# BKU.net
KiCad netlist of a schematic drawn in EAGLE
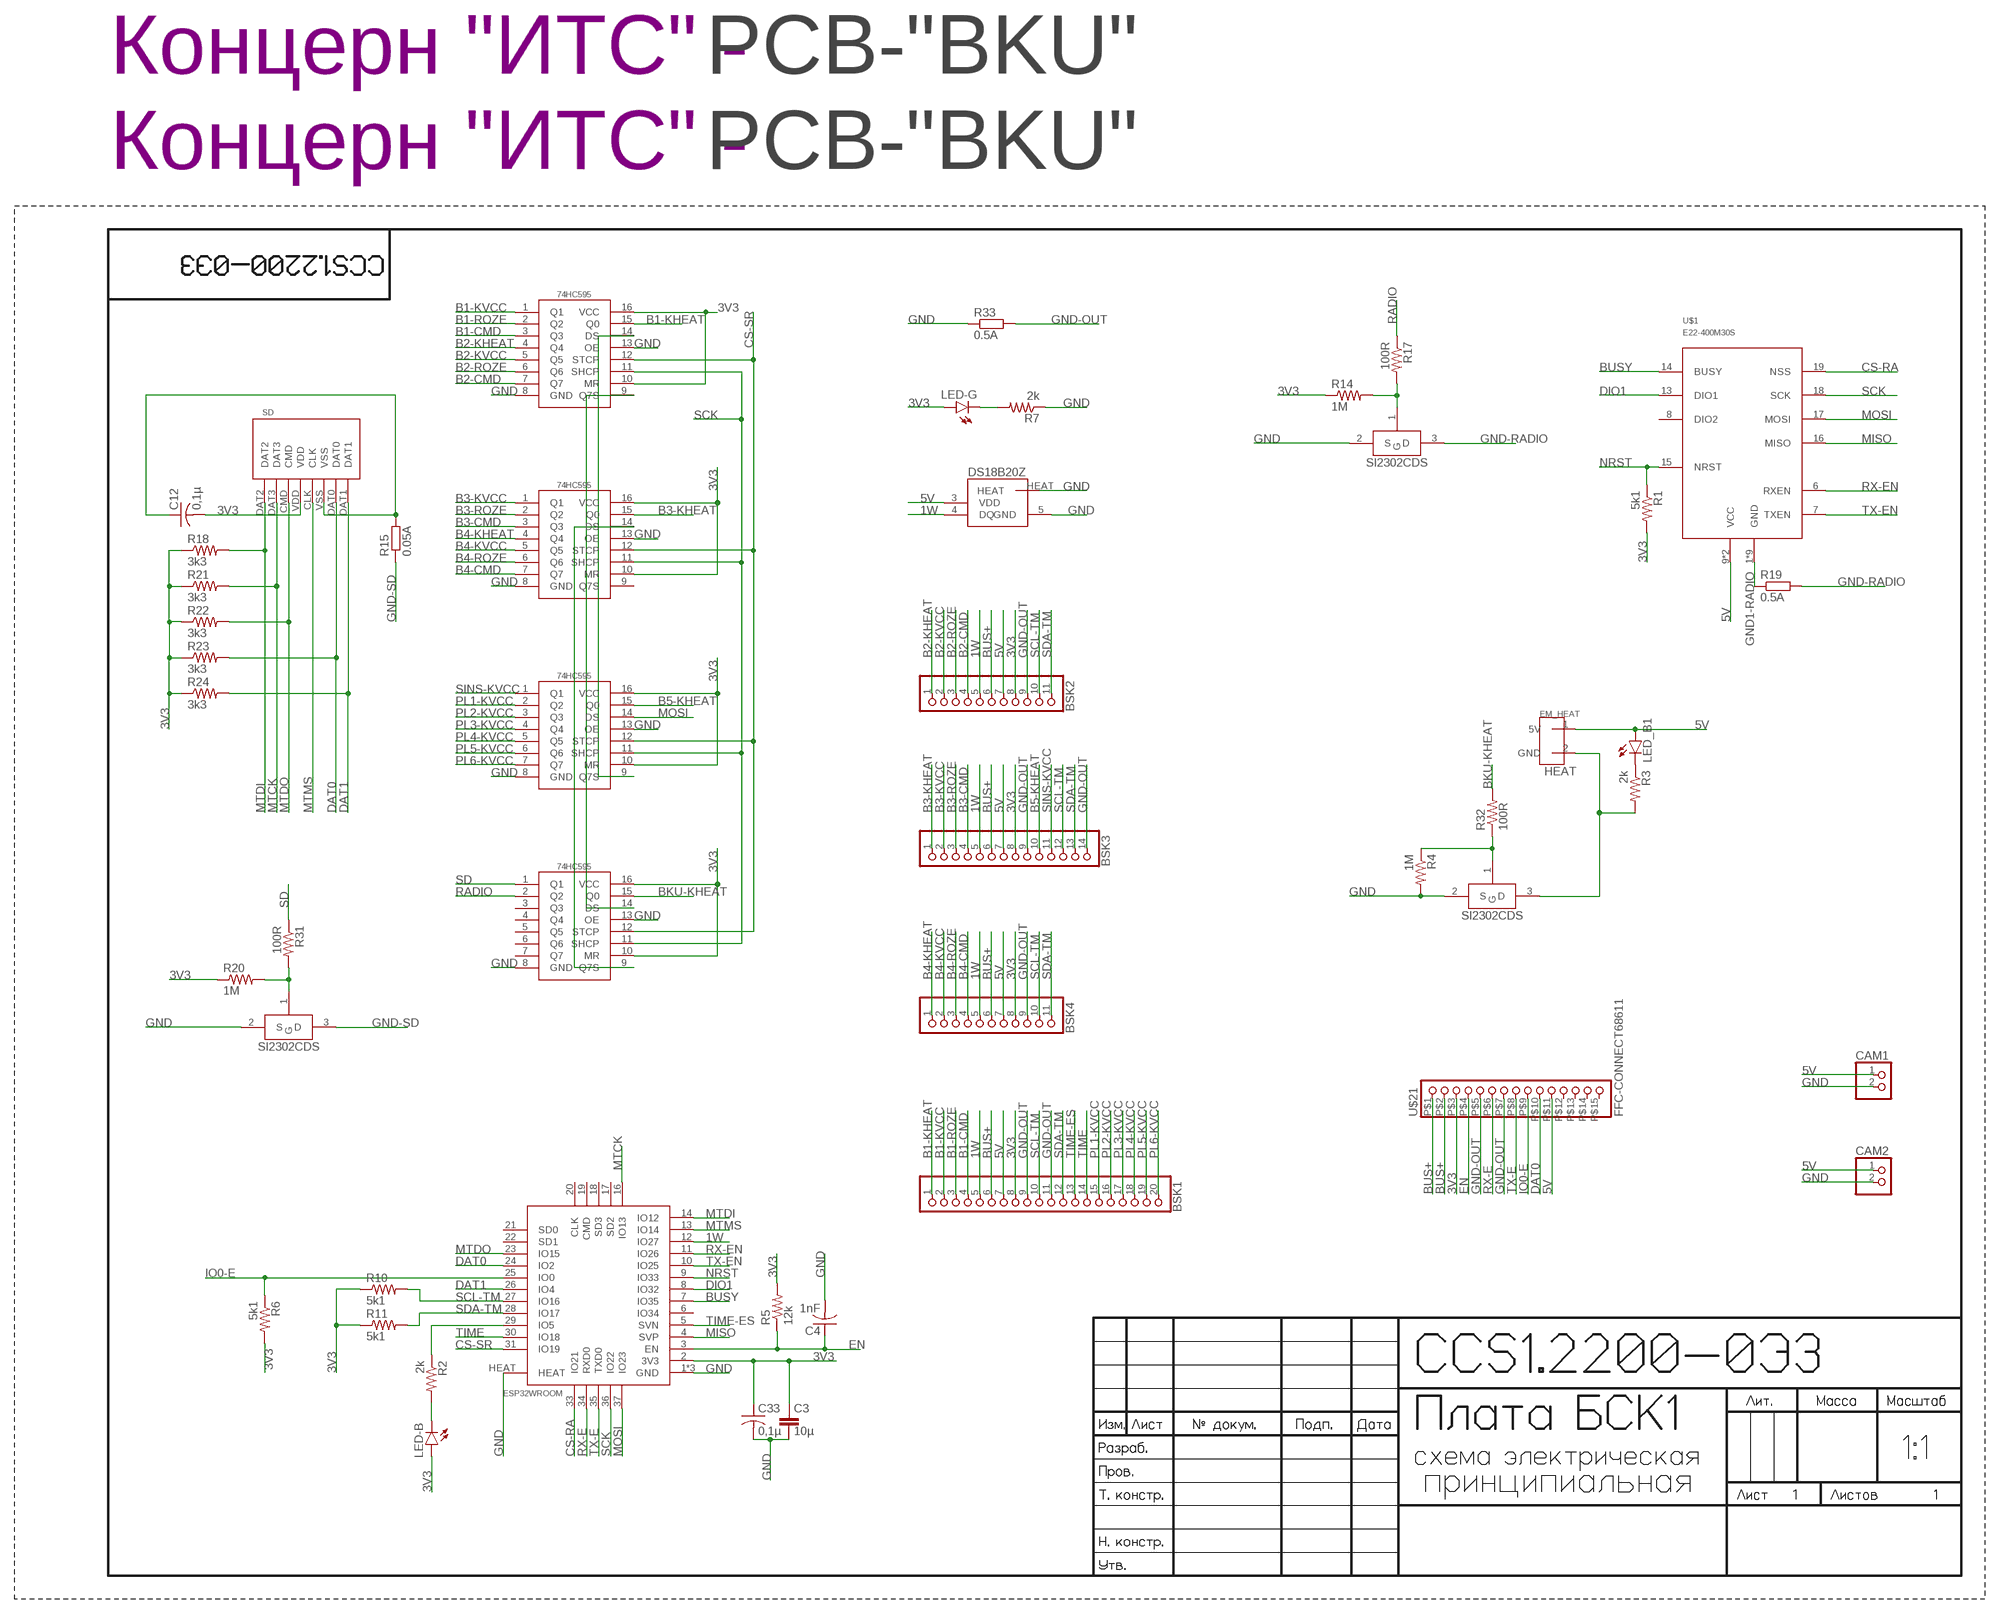
[diagram p0: schematic, sheet 1, part 1 of 2]
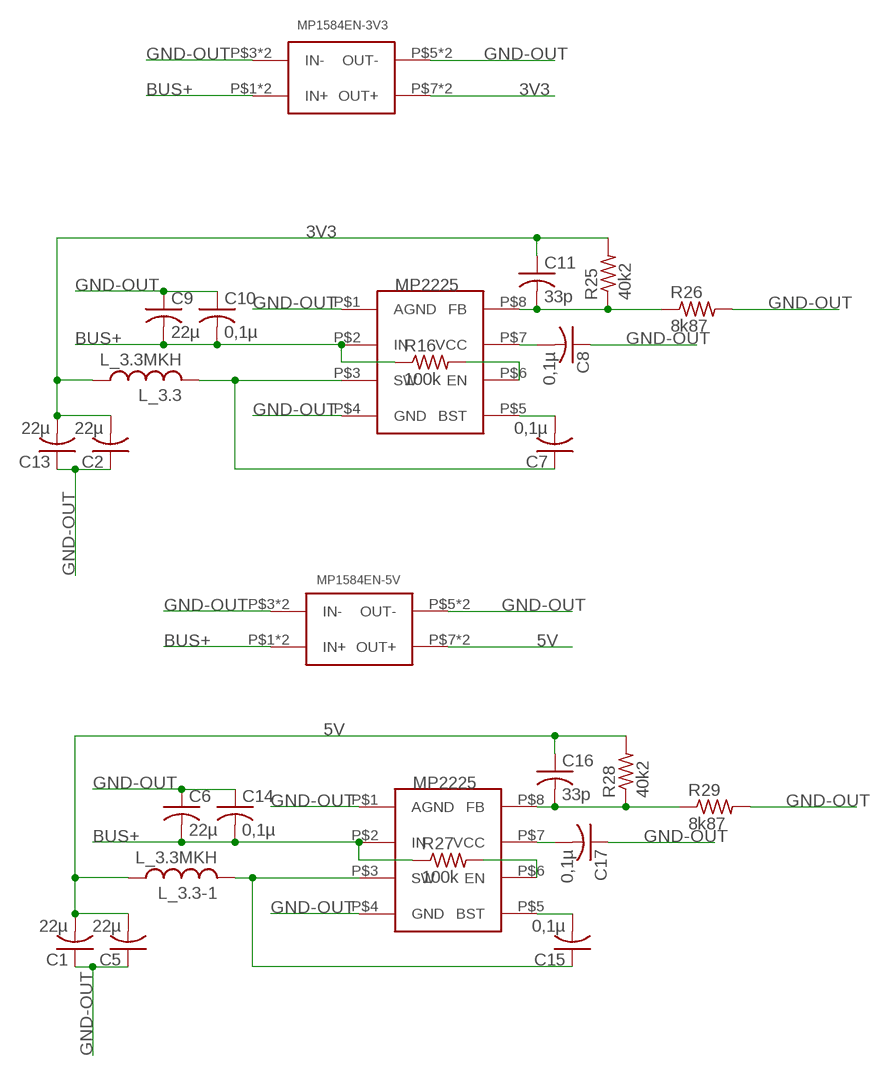
[diagram p1: schematic, sheet 1, part 2 of 2]

(export (version "E")
  (design (tool "Eeschema 10.0.6"))
  (components
    (comp (ref "74HC595#1")
      (value "74HC595")
      (footprint "eagle-import:TSSOP16")
      (libsource (lib "eagle-import") (part "74HC595"))
    )
    (comp (ref "74HC595#2")
      (value "74HC595")
      (footprint "eagle-import:TSSOP16")
      (libsource (lib "eagle-import") (part "74HC595"))
    )
    (comp (ref "74HC595#3")
      (value "74HC595")
      (footprint "eagle-import:TSSOP16")
      (libsource (lib "eagle-import") (part "74HC595"))
    )
    (comp (ref "74HC595#4")
      (value "74HC595")
      (footprint "eagle-import:TSSOP16")
      (libsource (lib "eagle-import") (part "74HC595"))
    )
    (comp (ref "BSK1")
      (value "PINHD-1X20")
      (footprint "eagle-import:1X20")
      (libsource (lib "eagle-import") (part "PINHD-1X20"))
    )
    (comp (ref "BSK2")
      (value "PINHD-1X11")
      (footprint "eagle-import:1X11")
      (libsource (lib "eagle-import") (part "PINHD-1X11"))
    )
    (comp (ref "BSK3")
      (value "PINHD-1X14")
      (footprint "eagle-import:1X14")
      (libsource (lib "eagle-import") (part "PINHD-1X14"))
    )
    (comp (ref "BSK4")
      (value "PINHD-1X11")
      (footprint "eagle-import:1X11")
      (libsource (lib "eagle-import") (part "PINHD-1X11"))
    )
    (comp (ref "C1")
      (value "22µ")
      (footprint "eagle-import:C1206")
      (libsource (lib "eagle-import") (part "C-USC1206"))
    )
    (comp (ref "C2")
      (value "22µ")
      (footprint "eagle-import:C1206")
      (libsource (lib "eagle-import") (part "C-USC1206"))
    )
    (comp (ref "C3")
      (value "10µ")
      (footprint "eagle-import:C1206")
      (libsource (lib "eagle-import") (part "C-EUC1206"))
    )
    (comp (ref "C4")
      (value "1nF")
      (footprint "eagle-import:C0603")
      (libsource (lib "eagle-import") (part "C-USC0603"))
    )
    (comp (ref "C5")
      (value "22µ")
      (footprint "eagle-import:C1206")
      (libsource (lib "eagle-import") (part "C-USC1206"))
    )
    (comp (ref "C6")
      (value "22µ")
      (footprint "eagle-import:C1206")
      (libsource (lib "eagle-import") (part "C-USC1206"))
    )
    (comp (ref "C7")
      (value "0,1µ")
      (footprint "eagle-import:C0603")
      (libsource (lib "eagle-import") (part "C-USC0603"))
    )
    (comp (ref "C8")
      (value "0,1µ")
      (footprint "eagle-import:C0603")
      (libsource (lib "eagle-import") (part "C-USC0603"))
    )
    (comp (ref "C9")
      (value "22µ")
      (footprint "eagle-import:C1206")
      (libsource (lib "eagle-import") (part "C-USC1206"))
    )
    (comp (ref "C10")
      (value "0,1µ")
      (footprint "eagle-import:C0603")
      (libsource (lib "eagle-import") (part "C-USC0603"))
    )
    (comp (ref "C11")
      (value "33p")
      (footprint "eagle-import:C0603")
      (libsource (lib "eagle-import") (part "C-USC0603"))
    )
    (comp (ref "C12")
      (value "0,1µ")
      (footprint "eagle-import:C0603")
      (libsource (lib "eagle-import") (part "C-USC0603"))
    )
    (comp (ref "C13")
      (value "22µ")
      (footprint "eagle-import:C1206")
      (libsource (lib "eagle-import") (part "C-USC1206"))
    )
    (comp (ref "C14")
      (value "0,1µ")
      (footprint "eagle-import:C0603")
      (libsource (lib "eagle-import") (part "C-USC0603"))
    )
    (comp (ref "C15")
      (value "0,1µ")
      (footprint "eagle-import:C0603")
      (libsource (lib "eagle-import") (part "C-USC0603"))
    )
    (comp (ref "C16")
      (value "33p")
      (footprint "eagle-import:C0603")
      (libsource (lib "eagle-import") (part "C-USC0603"))
    )
    (comp (ref "C17")
      (value "0,1µ")
      (footprint "eagle-import:C0603")
      (libsource (lib "eagle-import") (part "C-USC0603"))
    )
    (comp (ref "C33")
      (value "0,1µ")
      (footprint "eagle-import:C0603")
      (libsource (lib "eagle-import") (part "C-USC0603"))
    )
    (comp (ref "CAM1")
      (value "PINHD-1X2")
      (footprint "eagle-import:1X02")
      (libsource (lib "eagle-import") (part "PINHD-1X2"))
    )
    (comp (ref "CAM2")
      (value "PINHD-1X2")
      (footprint "eagle-import:1X02")
      (libsource (lib "eagle-import") (part "PINHD-1X2"))
    )
    (comp (ref "LED-B")
      (value "LEDCHIPLED_0603")
      (footprint "eagle-import:CHIPLED_0603")
      (libsource (lib "eagle-import") (part "LEDCHIPLED_0603"))
    )
    (comp (ref "LED-G")
      (value "LEDCHIPLED_0603")
      (footprint "eagle-import:CHIPLED_0603")
      (libsource (lib "eagle-import") (part "LEDCHIPLED_0603"))
    )
    (comp (ref "LED_B1")
      (value "LEDCHIPLED_0603")
      (footprint "eagle-import:CHIPLED_0603")
      (libsource (lib "eagle-import") (part "LEDCHIPLED_0603"))
    )
    (comp (ref "L_3.3")
      (value "L_3.3MKH")
      (footprint "eagle-import:L_SPM5020")
      (libsource (lib "eagle-import") (part "L_3.3MKH_5X5"))
    )
    (comp (ref "L_3.3-1")
      (value "L_3.3MKH")
      (footprint "eagle-import:L_SPM5020")
      (libsource (lib "eagle-import") (part "L_3.3MKH_5X5"))
    )
    (comp (ref "MP1584EN-3V3")
      (value "MP1584-B")
      (footprint "eagle-import:MP1584-B")
      (libsource (lib "eagle-import") (part "MP1584-B"))
    )
    (comp (ref "MP1584EN-5V")
      (value "MP1584-B")
      (footprint "eagle-import:MP1584-B")
      (libsource (lib "eagle-import") (part "MP1584-B"))
    )
    (comp (ref "MP2225-3V3")
      (value "MP2225")
      (footprint "eagle-import:TSOT23-8")
      (libsource (lib "eagle-import") (part "MP2225"))
    )
    (comp (ref "MP2225-5V")
      (value "MP2225")
      (footprint "eagle-import:TSOT23-8")
      (libsource (lib "eagle-import") (part "MP2225"))
    )
    (comp (ref "R1")
      (value "5k1")
      (footprint "eagle-import:R0603")
      (libsource (lib "eagle-import") (part "resistor_348_R-US_R0603"))
    )
    (comp (ref "R2")
      (value "2k")
      (footprint "eagle-import:R0603")
      (libsource (lib "eagle-import") (part "resistor_348_R-US_R0603"))
    )
    (comp (ref "R3")
      (value "2k")
      (footprint "eagle-import:R0603")
      (libsource (lib "eagle-import") (part "R-US_R0603"))
    )
    (comp (ref "R4")
      (value "1M")
      (footprint "eagle-import:R0603")
      (libsource (lib "eagle-import") (part "R-US_R0603"))
    )
    (comp (ref "R5")
      (value "12k")
      (footprint "eagle-import:R0603")
      (libsource (lib "eagle-import") (part "resistor_348_R-US_R0603"))
    )
    (comp (ref "R6")
      (value "5k1")
      (footprint "eagle-import:R0603")
      (libsource (lib "eagle-import") (part "resistor_348_R-US_R0603"))
    )
    (comp (ref "R7")
      (value "2k")
      (footprint "eagle-import:R0603")
      (libsource (lib "eagle-import") (part "resistor_348_R-US_R0603"))
    )
    (comp (ref "R10")
      (value "5k1")
      (footprint "eagle-import:R0603")
      (libsource (lib "eagle-import") (part "resistor_348_R-US_R0603"))
    )
    (comp (ref "R11")
      (value "5k1")
      (footprint "eagle-import:R0603")
      (libsource (lib "eagle-import") (part "resistor_348_R-US_R0603"))
    )
    (comp (ref "R14")
      (value "1M")
      (footprint "eagle-import:R0603")
      (libsource (lib "eagle-import") (part "R-US_R0603"))
    )
    (comp (ref "R15")
      (value "0.05A")
      (footprint "eagle-import:R1210")
      (libsource (lib "eagle-import") (part "R-EU_R1210"))
    )
    (comp (ref "R16")
      (value "100k")
      (footprint "eagle-import:R0603")
      (libsource (lib "eagle-import") (part "resistor_348_R-US_R0603"))
    )
    (comp (ref "R17")
      (value "100R")
      (footprint "eagle-import:R0603")
      (libsource (lib "eagle-import") (part "R-US_R0603"))
    )
    (comp (ref "R18")
      (value "3k3")
      (footprint "eagle-import:R0603")
      (libsource (lib "eagle-import") (part "resistor_348_R-US_R0603"))
    )
    (comp (ref "R19")
      (value "0.5A")
      (footprint "eagle-import:R1210")
      (libsource (lib "eagle-import") (part "R-EU_R1210"))
    )
    (comp (ref "R20")
      (value "1M")
      (footprint "eagle-import:R0603")
      (libsource (lib "eagle-import") (part "R-US_R0603"))
    )
    (comp (ref "R21")
      (value "3k3")
      (footprint "eagle-import:R0603")
      (libsource (lib "eagle-import") (part "resistor_348_R-US_R0603"))
    )
    (comp (ref "R22")
      (value "3k3")
      (footprint "eagle-import:R0603")
      (libsource (lib "eagle-import") (part "resistor_348_R-US_R0603"))
    )
    (comp (ref "R23")
      (value "3k3")
      (footprint "eagle-import:R0603")
      (libsource (lib "eagle-import") (part "resistor_348_R-US_R0603"))
    )
    (comp (ref "R24")
      (value "3k3")
      (footprint "eagle-import:R0603")
      (libsource (lib "eagle-import") (part "resistor_348_R-US_R0603"))
    )
    (comp (ref "R25")
      (value "40k2")
      (footprint "eagle-import:R0603")
      (libsource (lib "eagle-import") (part "resistor_348_R-US_R0603"))
    )
    (comp (ref "R26")
      (value "8k87")
      (footprint "eagle-import:R0603")
      (libsource (lib "eagle-import") (part "resistor_348_R-US_R0603"))
    )
    (comp (ref "R27")
      (value "100k")
      (footprint "eagle-import:R0603")
      (libsource (lib "eagle-import") (part "resistor_348_R-US_R0603"))
    )
    (comp (ref "R28")
      (value "40k2")
      (footprint "eagle-import:R0603")
      (libsource (lib "eagle-import") (part "resistor_348_R-US_R0603"))
    )
    (comp (ref "R29")
      (value "8k87")
      (footprint "eagle-import:R0603")
      (libsource (lib "eagle-import") (part "resistor_348_R-US_R0603"))
    )
    (comp (ref "R31")
      (value "100R")
      (footprint "eagle-import:R0603")
      (libsource (lib "eagle-import") (part "R-US_R0603"))
    )
    (comp (ref "R32")
      (value "100R")
      (footprint "eagle-import:R0603")
      (libsource (lib "eagle-import") (part "R-US_R0603"))
    )
    (comp (ref "R33")
      (value "0.5A")
      (footprint "eagle-import:R1210")
      (libsource (lib "eagle-import") (part "R-EU_R1210"))
    )
    (comp (ref "SD") (value "SD") (footprint "eagle-import:SD") (libsource (lib "eagle-import") (part "SD")))
    (comp (ref "U$1")
      (value "E22-400M30S")
      (footprint "eagle-import:E22-400M30S")
      (libsource (lib "eagle-import") (part "E22-400M30S"))
    )
    (comp (ref "U$2")
      (value "PCB-\"BKU\"")
      (footprint "eagle-import:ITS-LOGO")
      (libsource (lib "eagle-import") (part "ITS-LOGOPCB-{dblquote}{dblquote}"))
    )
    (comp (ref "U$3")
      (value "SI2302CDS")
      (footprint "eagle-import:SOT23-3")
      (libsource (lib "eagle-import") (part "SI2302CDS"))
    )
    (comp (ref "U$4")
      (value "SI2302CDS")
      (footprint "eagle-import:SOT23-3")
      (libsource (lib "eagle-import") (part "SI2302CDS"))
    )
    (comp (ref "U$5")
      (value "DS18B20Z")
      (footprint "eagle-import:SOIC8+HEAT_S")
      (libsource (lib "eagle-import") (part "DS18B20Z"))
    )
    (comp (ref "U$6")
      (value "PCB-\"BKU\"")
      (footprint "eagle-import:ITS-LOGO")
      (libsource (lib "eagle-import") (part "ITS-LOGOPCB-{dblquote}{dblquote}"))
    )
    (comp (ref "U$13")
      (value "ESP32WROOM")
      (footprint "eagle-import:ESP32WROOM")
      (libsource (lib "eagle-import") (part "ESP32WROOM"))
    )
    (comp (ref "U$21")
      (value "FFC-CONNECT68611")
      (footprint "eagle-import:68611")
      (libsource (lib "eagle-import") (part "FFC-CONNECT68611"))
    )
    (comp (ref "U$23")
      (value "SI2302CDS")
      (footprint "eagle-import:SOT23-3")
      (libsource (lib "eagle-import") (part "SI2302CDS"))
    )
    (comp (ref "U$24")
      (value "EM_HEAT")
      (footprint "eagle-import:EM_HEAT")
      (libsource (lib "eagle-import") (part "EM_HEAT"))
    )
  )
  (nets
    (net (code "1") (name "/1W") (class "Default")
      (node (ref "BSK1") (pin "5") (pinfunction "5_5") (pintype "passive"))
      (node (ref "BSK2") (pin "5") (pinfunction "5_5") (pintype "passive"))
      (node (ref "BSK3") (pin "5") (pinfunction "5_5") (pintype "passive"))
      (node (ref "BSK4") (pin "5") (pinfunction "5_5") (pintype "passive"))
      (node (ref "U$13") (pin "12") (pinfunction "IO27_12") (pintype "bidirectional"))
      (node (ref "U$5") (pin "4") (pinfunction "DQ_4") (pintype "bidirectional"))
    )
    (net (code "2") (name "/3V3") (class "Default")
      (node (ref "74HC595#1") (pin "10") (pinfunction "MR_10") (pintype "bidirectional"))
      (node (ref "74HC595#1") (pin "16") (pinfunction "VCC_16") (pintype "bidirectional"))
      (node (ref "74HC595#2") (pin "10") (pinfunction "MR_10") (pintype "bidirectional"))
      (node (ref "74HC595#2") (pin "16") (pinfunction "VCC_16") (pintype "bidirectional"))
      (node (ref "74HC595#3") (pin "10") (pinfunction "MR_10") (pintype "bidirectional"))
      (node (ref "74HC595#3") (pin "16") (pinfunction "VCC_16") (pintype "bidirectional"))
      (node (ref "74HC595#4") (pin "10") (pinfunction "MR_10") (pintype "bidirectional"))
      (node (ref "74HC595#4") (pin "16") (pinfunction "VCC_16") (pintype "bidirectional"))
      (node (ref "BSK1") (pin "8") (pinfunction "8_8") (pintype "passive"))
      (node (ref "BSK2") (pin "8") (pinfunction "8_8") (pintype "passive"))
      (node (ref "BSK3") (pin "8") (pinfunction "8_8") (pintype "passive"))
      (node (ref "BSK4") (pin "8") (pinfunction "8_8") (pintype "passive"))
      (node (ref "C11") (pin "1") (pinfunction "1_1") (pintype "passive"))
      (node (ref "C12") (pin "2") (pinfunction "2_2") (pintype "passive"))
      (node (ref "C13") (pin "2") (pinfunction "2_2") (pintype "passive"))
      (node (ref "C2") (pin "2") (pinfunction "2_2") (pintype "passive"))
      (node (ref "C3") (pin "1") (pinfunction "1_1") (pintype "passive"))
      (node (ref "C33") (pin "1") (pinfunction "1_1") (pintype "passive"))
      (node (ref "LED-B") (pin "A") (pinfunction "A_A") (pintype "passive"))
      (node (ref "LED-G") (pin "A") (pinfunction "A_A") (pintype "passive"))
      (node (ref "L_3.3") (pin "P$1") (pinfunction "1_P$1") (pintype "passive"))
      (node (ref "MP1584EN-3V3") (pin "P$7") (pinfunction "OUT+_P$7") (pintype "bidirectional"))
      (node (ref "MP1584EN-3V3") (pin "P$8") (pinfunction "OUT+_P$8") (pintype "bidirectional"))
      (node (ref "R1") (pin "2") (pinfunction "2_2") (pintype "passive"))
      (node (ref "R10") (pin "1") (pinfunction "1_1") (pintype "passive"))
      (node (ref "R11") (pin "1") (pinfunction "1_1") (pintype "passive"))
      (node (ref "R14") (pin "1") (pinfunction "1_1") (pintype "passive"))
      (node (ref "R18") (pin "1") (pinfunction "1_1") (pintype "passive"))
      (node (ref "R20") (pin "1") (pinfunction "1_1") (pintype "passive"))
      (node (ref "R21") (pin "1") (pinfunction "1_1") (pintype "passive"))
      (node (ref "R22") (pin "1") (pinfunction "1_1") (pintype "passive"))
      (node (ref "R23") (pin "1") (pinfunction "1_1") (pintype "passive"))
      (node (ref "R24") (pin "1") (pinfunction "1_1") (pintype "passive"))
      (node (ref "R25") (pin "2") (pinfunction "2_2") (pintype "passive"))
      (node (ref "R5") (pin "2") (pinfunction "2_2") (pintype "passive"))
      (node (ref "R6") (pin "2") (pinfunction "2_2") (pintype "passive"))
      (node (ref "SD") (pin "VDD") (pinfunction "VDD_VDD") (pintype "bidirectional"))
      (node (ref "U$13") (pin "2") (pinfunction "3V3_2") (pintype "bidirectional"))
      (node (ref "U$21") (pin "P$3") (pinfunction "3_P$3") (pintype "passive"))
    )
    (net (code "3") (name "/5V") (class "Default")
      (node (ref "BSK1") (pin "7") (pinfunction "7_7") (pintype "passive"))
      (node (ref "BSK2") (pin "7") (pinfunction "7_7") (pintype "passive"))
      (node (ref "BSK3") (pin "7") (pinfunction "7_7") (pintype "passive"))
      (node (ref "BSK4") (pin "7") (pinfunction "7_7") (pintype "passive"))
      (node (ref "C1") (pin "2") (pinfunction "2_2") (pintype "passive"))
      (node (ref "C16") (pin "1") (pinfunction "1_1") (pintype "passive"))
      (node (ref "C5") (pin "2") (pinfunction "2_2") (pintype "passive"))
      (node (ref "CAM1") (pin "1") (pinfunction "1_1") (pintype "passive"))
      (node (ref "CAM2") (pin "1") (pinfunction "1_1") (pintype "passive"))
      (node (ref "LED_B1") (pin "A") (pinfunction "A_A") (pintype "passive"))
      (node (ref "L_3.3-1") (pin "P$1") (pinfunction "1_P$1") (pintype "passive"))
      (node (ref "MP1584EN-5V") (pin "P$7") (pinfunction "OUT+_P$7") (pintype "bidirectional"))
      (node (ref "MP1584EN-5V") (pin "P$8") (pinfunction "OUT+_P$8") (pintype "bidirectional"))
      (node (ref "R28") (pin "2") (pinfunction "2_2") (pintype "passive"))
      (node (ref "U$1") (pin "10") (pinfunction "VCC_10") (pintype "power_in"))
      (node (ref "U$1") (pin "9") (pinfunction "VCC_9") (pintype "power_in"))
      (node (ref "U$21") (pin "P$11") (pinfunction "11_P$11") (pintype "passive"))
      (node (ref "U$24") (pin "1") (pinfunction "5V_1") (pintype "bidirectional"))
      (node (ref "U$5") (pin "3") (pinfunction "VDD_3") (pintype "bidirectional"))
    )
    (net (code "4") (name "/B1-CMD") (class "Default")
      (node (ref "74HC595#1") (pin "3") (pinfunction "Q3_3") (pintype "bidirectional"))
      (node (ref "BSK1") (pin "4") (pinfunction "4_4") (pintype "passive"))
    )
    (net (code "5") (name "/B1-KHEAT") (class "Default")
      (node (ref "74HC595#1") (pin "15") (pinfunction "Q0_15") (pintype "bidirectional"))
      (node (ref "BSK1") (pin "1") (pinfunction "1_1") (pintype "passive"))
    )
    (net (code "6") (name "/B1-KVCC") (class "Default")
      (node (ref "74HC595#1") (pin "1") (pinfunction "Q1_1") (pintype "bidirectional"))
      (node (ref "BSK1") (pin "2") (pinfunction "2_2") (pintype "passive"))
    )
    (net (code "7") (name "/B1-ROZE") (class "Default")
      (node (ref "74HC595#1") (pin "2") (pinfunction "Q2_2") (pintype "bidirectional"))
      (node (ref "BSK1") (pin "3") (pinfunction "3_3") (pintype "passive"))
    )
    (net (code "8") (name "/B2-CMD") (class "Default")
      (node (ref "74HC595#1") (pin "7") (pinfunction "Q7_7") (pintype "bidirectional"))
      (node (ref "BSK2") (pin "4") (pinfunction "4_4") (pintype "passive"))
    )
    (net (code "9") (name "/B2-KHEAT") (class "Default")
      (node (ref "74HC595#1") (pin "4") (pinfunction "Q4_4") (pintype "bidirectional"))
      (node (ref "BSK2") (pin "1") (pinfunction "1_1") (pintype "passive"))
    )
    (net (code "10") (name "/B2-KVCC") (class "Default")
      (node (ref "74HC595#1") (pin "5") (pinfunction "Q5_5") (pintype "bidirectional"))
      (node (ref "BSK2") (pin "2") (pinfunction "2_2") (pintype "passive"))
    )
    (net (code "11") (name "/B2-ROZE") (class "Default")
      (node (ref "74HC595#1") (pin "6") (pinfunction "Q6_6") (pintype "bidirectional"))
      (node (ref "BSK2") (pin "3") (pinfunction "3_3") (pintype "passive"))
    )
    (net (code "12") (name "/B3-CMD") (class "Default")
      (node (ref "74HC595#2") (pin "3") (pinfunction "Q3_3") (pintype "bidirectional"))
      (node (ref "BSK3") (pin "4") (pinfunction "4_4") (pintype "passive"))
    )
    (net (code "13") (name "/B3-KHEAT") (class "Default")
      (node (ref "74HC595#2") (pin "15") (pinfunction "Q0_15") (pintype "bidirectional"))
      (node (ref "BSK3") (pin "1") (pinfunction "1_1") (pintype "passive"))
    )
    (net (code "14") (name "/B3-KVCC") (class "Default")
      (node (ref "74HC595#2") (pin "1") (pinfunction "Q1_1") (pintype "bidirectional"))
      (node (ref "BSK3") (pin "2") (pinfunction "2_2") (pintype "passive"))
    )
    (net (code "15") (name "/B3-ROZE") (class "Default")
      (node (ref "74HC595#2") (pin "2") (pinfunction "Q2_2") (pintype "bidirectional"))
      (node (ref "BSK3") (pin "3") (pinfunction "3_3") (pintype "passive"))
    )
    (net (code "16") (name "/B4-CMD") (class "Default")
      (node (ref "74HC595#2") (pin "7") (pinfunction "Q7_7") (pintype "bidirectional"))
      (node (ref "BSK4") (pin "4") (pinfunction "4_4") (pintype "passive"))
    )
    (net (code "17") (name "/B4-KHEAT") (class "Default")
      (node (ref "74HC595#2") (pin "4") (pinfunction "Q4_4") (pintype "bidirectional"))
      (node (ref "BSK4") (pin "1") (pinfunction "1_1") (pintype "passive"))
    )
    (net (code "18") (name "/B4-KVCC") (class "Default")
      (node (ref "74HC595#2") (pin "5") (pinfunction "Q5_5") (pintype "bidirectional"))
      (node (ref "BSK4") (pin "2") (pinfunction "2_2") (pintype "passive"))
    )
    (net (code "19") (name "/B4-ROZE") (class "Default")
      (node (ref "74HC595#2") (pin "6") (pinfunction "Q6_6") (pintype "bidirectional"))
      (node (ref "BSK4") (pin "3") (pinfunction "3_3") (pintype "passive"))
    )
    (net (code "20") (name "/B5-KHEAT") (class "Default")
      (node (ref "74HC595#3") (pin "15") (pinfunction "Q0_15") (pintype "bidirectional"))
      (node (ref "BSK3") (pin "10") (pinfunction "10_10") (pintype "passive"))
    )
    (net (code "21") (name "/BKU-KHEAT") (class "Default")
      (node (ref "74HC595#4") (pin "15") (pinfunction "Q0_15") (pintype "bidirectional"))
      (node (ref "R32") (pin "2") (pinfunction "2_2") (pintype "passive"))
    )
    (net (code "22") (name "/BUS+") (class "Default")
      (node (ref "BSK1") (pin "6") (pinfunction "6_6") (pintype "passive"))
      (node (ref "BSK2") (pin "6") (pinfunction "6_6") (pintype "passive"))
      (node (ref "BSK3") (pin "6") (pinfunction "6_6") (pintype "passive"))
      (node (ref "BSK4") (pin "6") (pinfunction "6_6") (pintype "passive"))
      (node (ref "C10") (pin "2") (pinfunction "2_2") (pintype "passive"))
      (node (ref "C14") (pin "2") (pinfunction "2_2") (pintype "passive"))
      (node (ref "C6") (pin "2") (pinfunction "2_2") (pintype "passive"))
      (node (ref "C9") (pin "2") (pinfunction "2_2") (pintype "passive"))
      (node (ref "MP1584EN-3V3") (pin "P$1") (pinfunction "IN+_P$1") (pintype "bidirectional"))
      (node (ref "MP1584EN-3V3") (pin "P$2") (pinfunction "IN+_P$2") (pintype "bidirectional"))
      (node (ref "MP1584EN-5V") (pin "P$1") (pinfunction "IN+_P$1") (pintype "bidirectional"))
      (node (ref "MP1584EN-5V") (pin "P$2") (pinfunction "IN+_P$2") (pintype "bidirectional"))
      (node (ref "MP2225-3V3") (pin "P$2") (pinfunction "IN_P$2") (pintype "bidirectional"))
      (node (ref "MP2225-5V") (pin "P$2") (pinfunction "IN_P$2") (pintype "bidirectional"))
      (node (ref "R16") (pin "1") (pinfunction "1_1") (pintype "passive"))
      (node (ref "R27") (pin "1") (pinfunction "1_1") (pintype "passive"))
      (node (ref "U$21") (pin "P$1") (pinfunction "1_P$1") (pintype "passive"))
      (node (ref "U$21") (pin "P$2") (pinfunction "2_P$2") (pintype "passive"))
    )
    (net (code "23") (name "/BUSY") (class "Default")
      (node (ref "U$1") (pin "14") (pinfunction "BUSY_14") (pintype "output"))
      (node (ref "U$13") (pin "7") (pinfunction "IO35_7") (pintype "bidirectional"))
    )
    (net (code "24") (name "/CS-RA") (class "Default")
      (node (ref "U$1") (pin "19") (pinfunction "NSS_19") (pintype "input"))
      (node (ref "U$13") (pin "33") (pinfunction "IO21_33") (pintype "bidirectional"))
    )
    (net (code "25") (name "/CS-SR") (class "Default")
      (node (ref "74HC595#1") (pin "12") (pinfunction "STCP_12") (pintype "bidirectional"))
      (node (ref "74HC595#2") (pin "12") (pinfunction "STCP_12") (pintype "bidirectional"))
      (node (ref "74HC595#3") (pin "12") (pinfunction "STCP_12") (pintype "bidirectional"))
      (node (ref "74HC595#4") (pin "12") (pinfunction "STCP_12") (pintype "bidirectional"))
      (node (ref "U$13") (pin "31") (pinfunction "IO19_31") (pintype "bidirectional"))
    )
    (net (code "26") (name "/DAT0") (class "Default")
      (node (ref "R23") (pin "2") (pinfunction "2_2") (pintype "passive"))
      (node (ref "SD") (pin "DAT0") (pinfunction "DAT0_DAT0") (pintype "bidirectional"))
      (node (ref "U$13") (pin "24") (pinfunction "IO2_24") (pintype "bidirectional"))
      (node (ref "U$21") (pin "P$10") (pinfunction "10_P$10") (pintype "passive"))
    )
    (net (code "27") (name "/DAT1") (class "Default")
      (node (ref "R24") (pin "2") (pinfunction "2_2") (pintype "passive"))
      (node (ref "SD") (pin "DAT1") (pinfunction "DAT1_DAT1") (pintype "bidirectional"))
      (node (ref "U$13") (pin "26") (pinfunction "IO4_26") (pintype "bidirectional"))
    )
    (net (code "28") (name "/DIO1") (class "Default")
      (node (ref "U$1") (pin "13") (pinfunction "DIO1_13") (pintype "bidirectional"))
      (node (ref "U$13") (pin "8") (pinfunction "IO32_8") (pintype "bidirectional"))
    )
    (net (code "29") (name "/EN") (class "Default")
      (node (ref "C4") (pin "1") (pinfunction "1_1") (pintype "passive"))
      (node (ref "R5") (pin "1") (pinfunction "1_1") (pintype "passive"))
      (node (ref "U$13") (pin "3") (pinfunction "EN_3") (pintype "bidirectional"))
      (node (ref "U$21") (pin "P$4") (pinfunction "4_P$4") (pintype "passive"))
    )
    (net (code "30") (name "/GND") (class "Default")
      (node (ref "74HC595#1") (pin "13") (pinfunction "OE_13") (pintype "bidirectional"))
      (node (ref "74HC595#1") (pin "8") (pinfunction "GND_8") (pintype "bidirectional"))
      (node (ref "74HC595#2") (pin "13") (pinfunction "OE_13") (pintype "bidirectional"))
      (node (ref "74HC595#2") (pin "8") (pinfunction "GND_8") (pintype "bidirectional"))
      (node (ref "74HC595#3") (pin "13") (pinfunction "OE_13") (pintype "bidirectional"))
      (node (ref "74HC595#3") (pin "8") (pinfunction "GND_8") (pintype "bidirectional"))
      (node (ref "74HC595#4") (pin "13") (pinfunction "OE_13") (pintype "bidirectional"))
      (node (ref "74HC595#4") (pin "8") (pinfunction "GND_8") (pintype "bidirectional"))
      (node (ref "C3") (pin "2") (pinfunction "2_2") (pintype "passive"))
      (node (ref "C33") (pin "2") (pinfunction "2_2") (pintype "passive"))
      (node (ref "C4") (pin "2") (pinfunction "2_2") (pintype "passive"))
      (node (ref "CAM1") (pin "2") (pinfunction "2_2") (pintype "passive"))
      (node (ref "CAM2") (pin "2") (pinfunction "2_2") (pintype "passive"))
      (node (ref "R33") (pin "1") (pinfunction "1_1") (pintype "passive"))
      (node (ref "R4") (pin "2") (pinfunction "2_2") (pintype "passive"))
      (node (ref "R7") (pin "1") (pinfunction "1_1") (pintype "passive"))
      (node (ref "U$13") (pin "1") (pinfunction "GND_1") (pintype "bidirectional"))
      (node (ref "U$13") (pin "15") (pinfunction "GND_15") (pintype "bidirectional"))
      (node (ref "U$13") (pin "38") (pinfunction "GND_38") (pintype "bidirectional"))
      (node (ref "U$13") (pin "HEAT") (pinfunction "HEAT_HEAT") (pintype "bidirectional"))
      (node (ref "U$23") (pin "2") (pinfunction "S_2") (pintype "bidirectional"))
      (node (ref "U$3") (pin "2") (pinfunction "S_2") (pintype "bidirectional"))
      (node (ref "U$4") (pin "2") (pinfunction "S_2") (pintype "bidirectional"))
      (node (ref "U$5") (pin "5") (pinfunction "GND_5") (pintype "bidirectional"))
      (node (ref "U$5") (pin "HEAT") (pinfunction "HEAT_HEAT") (pintype "bidirectional"))
    )
    (net (code "31") (name "/GND-OUT") (class "Default")
      (node (ref "BSK1") (pin "11") (pinfunction "11_11") (pintype "passive"))
      (node (ref "BSK1") (pin "9") (pinfunction "9_9") (pintype "passive"))
      (node (ref "BSK2") (pin "9") (pinfunction "9_9") (pintype "passive"))
      (node (ref "BSK3") (pin "14") (pinfunction "14_14") (pintype "passive"))
      (node (ref "BSK3") (pin "9") (pinfunction "9_9") (pintype "passive"))
      (node (ref "BSK4") (pin "9") (pinfunction "9_9") (pintype "passive"))
      (node (ref "C1") (pin "1") (pinfunction "1_1") (pintype "passive"))
      (node (ref "C10") (pin "1") (pinfunction "1_1") (pintype "passive"))
      (node (ref "C13") (pin "1") (pinfunction "1_1") (pintype "passive"))
      (node (ref "C14") (pin "1") (pinfunction "1_1") (pintype "passive"))
      (node (ref "C17") (pin "1") (pinfunction "1_1") (pintype "passive"))
      (node (ref "C2") (pin "1") (pinfunction "1_1") (pintype "passive"))
      (node (ref "C5") (pin "1") (pinfunction "1_1") (pintype "passive"))
      (node (ref "C6") (pin "1") (pinfunction "1_1") (pintype "passive"))
      (node (ref "C8") (pin "1") (pinfunction "1_1") (pintype "passive"))
      (node (ref "C9") (pin "1") (pinfunction "1_1") (pintype "passive"))
      (node (ref "MP1584EN-3V3") (pin "P$3") (pinfunction "IN-_P$3") (pintype "bidirectional"))
      (node (ref "MP1584EN-3V3") (pin "P$4") (pinfunction "IN-_P$4") (pintype "bidirectional"))
      (node (ref "MP1584EN-3V3") (pin "P$5") (pinfunction "OUT-_P$5") (pintype "bidirectional"))
      (node (ref "MP1584EN-3V3") (pin "P$6") (pinfunction "OUT-_P$6") (pintype "bidirectional"))
      (node (ref "MP1584EN-5V") (pin "P$3") (pinfunction "IN-_P$3") (pintype "bidirectional"))
      (node (ref "MP1584EN-5V") (pin "P$4") (pinfunction "IN-_P$4") (pintype "bidirectional"))
      (node (ref "MP1584EN-5V") (pin "P$5") (pinfunction "OUT-_P$5") (pintype "bidirectional"))
      (node (ref "MP1584EN-5V") (pin "P$6") (pinfunction "OUT-_P$6") (pintype "bidirectional"))
      (node (ref "MP2225-3V3") (pin "P$1") (pinfunction "AGND_P$1") (pintype "bidirectional"))
      (node (ref "MP2225-3V3") (pin "P$4") (pinfunction "GND_P$4") (pintype "bidirectional"))
      (node (ref "MP2225-5V") (pin "P$1") (pinfunction "AGND_P$1") (pintype "bidirectional"))
      (node (ref "MP2225-5V") (pin "P$4") (pinfunction "GND_P$4") (pintype "bidirectional"))
      (node (ref "R26") (pin "2") (pinfunction "2_2") (pintype "passive"))
      (node (ref "R29") (pin "2") (pinfunction "2_2") (pintype "passive"))
      (node (ref "R33") (pin "2") (pinfunction "2_2") (pintype "passive"))
      (node (ref "U$21") (pin "P$5") (pinfunction "5_P$5") (pintype "passive"))
      (node (ref "U$21") (pin "P$7") (pinfunction "7_P$7") (pintype "passive"))
    )
    (net (code "32") (name "/GND-RADIO") (class "Default")
      (node (ref "R19") (pin "2") (pinfunction "2_2") (pintype "passive"))
      (node (ref "U$4") (pin "3") (pinfunction "D_3") (pintype "bidirectional"))
    )
    (net (code "33") (name "/GND-SD") (class "Default")
      (node (ref "R15") (pin "1") (pinfunction "1_1") (pintype "passive"))
      (node (ref "U$3") (pin "3") (pinfunction "D_3") (pintype "bidirectional"))
    )
    (net (code "34") (name "/GND1-RADIO") (class "Default")
      (node (ref "R19") (pin "1") (pinfunction "1_1") (pintype "passive"))
      (node (ref "U$1") (pin "1") (pinfunction "GND_1") (pintype "power_in"))
      (node (ref "U$1") (pin "11") (pinfunction "GND_11") (pintype "power_in"))
      (node (ref "U$1") (pin "12") (pinfunction "GND_12") (pintype "power_in"))
      (node (ref "U$1") (pin "2") (pinfunction "GND_2") (pintype "power_in"))
      (node (ref "U$1") (pin "20") (pinfunction "GND_20") (pintype "power_in"))
      (node (ref "U$1") (pin "22") (pinfunction "GND_22") (pintype "power_in"))
      (node (ref "U$1") (pin "3") (pinfunction "GND_3") (pintype "power_in"))
      (node (ref "U$1") (pin "4") (pinfunction "GND_4") (pintype "power_in"))
      (node (ref "U$1") (pin "5") (pinfunction "GND_5") (pintype "power_in"))
    )
    (net (code "35") (name "/IO0-E") (class "Default")
      (node (ref "R6") (pin "1") (pinfunction "1_1") (pintype "passive"))
      (node (ref "U$13") (pin "25") (pinfunction "IO0_25") (pintype "bidirectional"))
      (node (ref "U$21") (pin "P$9") (pinfunction "9_P$9") (pintype "passive"))
    )
    (net (code "36") (name "/MISO") (class "Default")
      (node (ref "U$1") (pin "16") (pinfunction "MISO_16") (pintype "output"))
      (node (ref "U$13") (pin "4") (pinfunction "SVP_4") (pintype "bidirectional"))
    )
    (net (code "37") (name "/MOSI") (class "Default")
      (node (ref "74HC595#3") (pin "14") (pinfunction "DS_14") (pintype "bidirectional"))
      (node (ref "U$1") (pin "17") (pinfunction "MOSI_17") (pintype "input"))
      (node (ref "U$13") (pin "37") (pinfunction "IO23_37") (pintype "bidirectional"))
    )
    (net (code "38") (name "/MTCK") (class "Default")
      (node (ref "R21") (pin "2") (pinfunction "2_2") (pintype "passive"))
      (node (ref "SD") (pin "DAT3") (pinfunction "DAT3_DAT3") (pintype "bidirectional"))
      (node (ref "U$13") (pin "16") (pinfunction "IO13_16") (pintype "bidirectional"))
    )
    (net (code "39") (name "/MTDI") (class "Default")
      (node (ref "R18") (pin "2") (pinfunction "2_2") (pintype "passive"))
      (node (ref "SD") (pin "DAT2") (pinfunction "DAT2_DAT2") (pintype "bidirectional"))
      (node (ref "U$13") (pin "14") (pinfunction "IO12_14") (pintype "bidirectional"))
    )
    (net (code "40") (name "/MTDO") (class "Default")
      (node (ref "R22") (pin "2") (pinfunction "2_2") (pintype "passive"))
      (node (ref "SD") (pin "CMD") (pinfunction "CMD_CMD") (pintype "bidirectional"))
      (node (ref "U$13") (pin "23") (pinfunction "IO15_23") (pintype "bidirectional"))
    )
    (net (code "41") (name "/MTMS") (class "Default")
      (node (ref "SD") (pin "CLK") (pinfunction "CLK_CLK") (pintype "bidirectional"))
      (node (ref "U$13") (pin "13") (pinfunction "IO14_13") (pintype "bidirectional"))
    )
    (net (code "42") (name "/NRST") (class "Default")
      (node (ref "R1") (pin "1") (pinfunction "1_1") (pintype "passive"))
      (node (ref "U$1") (pin "15") (pinfunction "NRST_15") (pintype "input"))
      (node (ref "U$13") (pin "9") (pinfunction "IO33_9") (pintype "bidirectional"))
    )
    (net (code "43") (name "/PL1-KVCC") (class "Default")
      (node (ref "74HC595#3") (pin "2") (pinfunction "Q2_2") (pintype "bidirectional"))
      (node (ref "BSK1") (pin "15") (pinfunction "15_15") (pintype "passive"))
    )
    (net (code "44") (name "/PL2-KVCC") (class "Default")
      (node (ref "74HC595#3") (pin "3") (pinfunction "Q3_3") (pintype "bidirectional"))
      (node (ref "BSK1") (pin "16") (pinfunction "16_16") (pintype "passive"))
    )
    (net (code "45") (name "/PL3-KVCC") (class "Default")
      (node (ref "74HC595#3") (pin "4") (pinfunction "Q4_4") (pintype "bidirectional"))
      (node (ref "BSK1") (pin "17") (pinfunction "17_17") (pintype "passive"))
    )
    (net (code "46") (name "/PL4-KVCC") (class "Default")
      (node (ref "74HC595#3") (pin "5") (pinfunction "Q5_5") (pintype "bidirectional"))
      (node (ref "BSK1") (pin "18") (pinfunction "18_18") (pintype "passive"))
    )
    (net (code "47") (name "/PL5-KVCC") (class "Default")
      (node (ref "74HC595#3") (pin "6") (pinfunction "Q6_6") (pintype "bidirectional"))
      (node (ref "BSK1") (pin "19") (pinfunction "19_19") (pintype "passive"))
    )
    (net (code "48") (name "/PL6-KVCC") (class "Default")
      (node (ref "74HC595#3") (pin "7") (pinfunction "Q7_7") (pintype "bidirectional"))
      (node (ref "BSK1") (pin "20") (pinfunction "20_20") (pintype "passive"))
    )
    (net (code "49") (name "/RADIO") (class "Default")
      (node (ref "74HC595#4") (pin "2") (pinfunction "Q2_2") (pintype "bidirectional"))
      (node (ref "R17") (pin "1") (pinfunction "1_1") (pintype "passive"))
    )
    (net (code "50") (name "/RX-E") (class "Default")
      (node (ref "U$13") (pin "34") (pinfunction "RXD0_34") (pintype "bidirectional"))
      (node (ref "U$21") (pin "P$6") (pinfunction "6_P$6") (pintype "passive"))
    )
    (net (code "51") (name "/RX-EN") (class "Default")
      (node (ref "U$1") (pin "6") (pinfunction "RXEN_6") (pintype "input"))
      (node (ref "U$13") (pin "11") (pinfunction "IO26_11") (pintype "bidirectional"))
    )
    (net (code "52") (name "/SCK") (class "Default")
      (node (ref "74HC595#1") (pin "11") (pinfunction "SHCP_11") (pintype "bidirectional"))
      (node (ref "74HC595#2") (pin "11") (pinfunction "SHCP_11") (pintype "bidirectional"))
      (node (ref "74HC595#3") (pin "11") (pinfunction "SHCP_11") (pintype "bidirectional"))
      (node (ref "74HC595#4") (pin "11") (pinfunction "SHCP_11") (pintype "bidirectional"))
      (node (ref "U$1") (pin "18") (pinfunction "SCK_18") (pintype "input"))
      (node (ref "U$13") (pin "36") (pinfunction "IO22_36") (pintype "bidirectional"))
    )
    (net (code "53") (name "/SCL-TM") (class "Default")
      (node (ref "BSK1") (pin "10") (pinfunction "10_10") (pintype "passive"))
      (node (ref "BSK2") (pin "10") (pinfunction "10_10") (pintype "passive"))
      (node (ref "BSK3") (pin "12") (pinfunction "12_12") (pintype "passive"))
      (node (ref "BSK4") (pin "10") (pinfunction "10_10") (pintype "passive"))
      (node (ref "R10") (pin "2") (pinfunction "2_2") (pintype "passive"))
      (node (ref "U$13") (pin "27") (pinfunction "IO16_27") (pintype "bidirectional"))
    )
    (net (code "54") (name "/SD") (class "Default")
      (node (ref "74HC595#4") (pin "1") (pinfunction "Q1_1") (pintype "bidirectional"))
      (node (ref "R31") (pin "1") (pinfunction "1_1") (pintype "passive"))
    )
    (net (code "55") (name "/SDA-TM") (class "Default")
      (node (ref "BSK1") (pin "12") (pinfunction "12_12") (pintype "passive"))
      (node (ref "BSK2") (pin "11") (pinfunction "11_11") (pintype "passive"))
      (node (ref "BSK3") (pin "13") (pinfunction "13_13") (pintype "passive"))
      (node (ref "BSK4") (pin "11") (pinfunction "11_11") (pintype "passive"))
      (node (ref "R11") (pin "2") (pinfunction "2_2") (pintype "passive"))
      (node (ref "U$13") (pin "28") (pinfunction "IO17_28") (pintype "bidirectional"))
    )
    (net (code "56") (name "/SINS-KVCC") (class "Default")
      (node (ref "74HC595#3") (pin "1") (pinfunction "Q1_1") (pintype "bidirectional"))
      (node (ref "BSK3") (pin "11") (pinfunction "11_11") (pintype "passive"))
    )
    (net (code "57") (name "/TIME") (class "Default")
      (node (ref "BSK1") (pin "14") (pinfunction "14_14") (pintype "passive"))
      (node (ref "U$13") (pin "30") (pinfunction "IO18_30") (pintype "bidirectional"))
    )
    (net (code "58") (name "/TIME-ES") (class "Default")
      (node (ref "BSK1") (pin "13") (pinfunction "13_13") (pintype "passive"))
      (node (ref "U$13") (pin "5") (pinfunction "SVN_5") (pintype "bidirectional"))
    )
    (net (code "59") (name "/TX-E") (class "Default")
      (node (ref "U$13") (pin "35") (pinfunction "TXD0_35") (pintype "bidirectional"))
      (node (ref "U$21") (pin "P$8") (pinfunction "8_P$8") (pintype "passive"))
    )
    (net (code "60") (name "/TX-EN") (class "Default")
      (node (ref "U$1") (pin "7") (pinfunction "TXEN_7") (pintype "input"))
      (node (ref "U$13") (pin "10") (pinfunction "IO25_10") (pintype "bidirectional"))
    )
    (net (code "61") (name "Net-(74HC595#1-DS)") (class "Default")
      (node (ref "74HC595#1") (pin "14") (pinfunction "DS_14") (pintype "bidirectional"))
      (node (ref "74HC595#3") (pin "9") (pinfunction "Q7S_9") (pintype "bidirectional"))
    )
    (net (code "62") (name "Net-(74HC595#1-Q7S)") (class "Default")
      (node (ref "74HC595#1") (pin "9") (pinfunction "Q7S_9") (pintype "bidirectional"))
      (node (ref "74HC595#4") (pin "14") (pinfunction "DS_14") (pintype "bidirectional"))
    )
    (net (code "63") (name "Net-(74HC595#2-DS)") (class "Default")
      (node (ref "74HC595#2") (pin "14") (pinfunction "DS_14") (pintype "bidirectional"))
      (node (ref "74HC595#4") (pin "9") (pinfunction "Q7S_9") (pintype "bidirectional"))
    )
    (net (code "64") (name "Net-(C12-Pad1)") (class "Default")
      (node (ref "C12") (pin "1") (pinfunction "1_1") (pintype "passive"))
      (node (ref "R15") (pin "2") (pinfunction "2_2") (pintype "passive"))
      (node (ref "SD") (pin "VSS") (pinfunction "VSS_VSS") (pintype "bidirectional"))
    )
    (net (code "65") (name "Net-(LED-B-PadC)") (class "Default")
      (node (ref "LED-B") (pin "C") (pinfunction "C_C") (pintype "passive"))
      (node (ref "R2") (pin "2") (pinfunction "2_2") (pintype "passive"))
    )
    (net (code "66") (name "Net-(LED-G-PadC)") (class "Default")
      (node (ref "LED-G") (pin "C") (pinfunction "C_C") (pintype "passive"))
      (node (ref "R7") (pin "2") (pinfunction "2_2") (pintype "passive"))
    )
    (net (code "67") (name "Net-(LED_B1-PadC)") (class "Default")
      (node (ref "LED_B1") (pin "C") (pinfunction "C_C") (pintype "passive"))
      (node (ref "R3") (pin "1") (pinfunction "1_1") (pintype "passive"))
    )
    (net (code "68") (name "Net-(L_3.3-1-2)") (class "Default")
      (node (ref "C15") (pin "1") (pinfunction "1_1") (pintype "passive"))
      (node (ref "L_3.3-1") (pin "P$2") (pinfunction "2_P$2") (pintype "passive"))
      (node (ref "MP2225-5V") (pin "P$3") (pinfunction "SW_P$3") (pintype "bidirectional"))
    )
    (net (code "69") (name "Net-(L_3.3-2)") (class "Default")
      (node (ref "C7") (pin "1") (pinfunction "1_1") (pintype "passive"))
      (node (ref "L_3.3") (pin "P$2") (pinfunction "2_P$2") (pintype "passive"))
      (node (ref "MP2225-3V3") (pin "P$3") (pinfunction "SW_P$3") (pintype "bidirectional"))
    )
    (net (code "70") (name "Net-(MP2225-3V3-BST)") (class "Default")
      (node (ref "C7") (pin "2") (pinfunction "2_2") (pintype "passive"))
      (node (ref "MP2225-3V3") (pin "P$5") (pinfunction "BST_P$5") (pintype "bidirectional"))
    )
    (net (code "71") (name "Net-(MP2225-3V3-EN)") (class "Default")
      (node (ref "MP2225-3V3") (pin "P$6") (pinfunction "EN_P$6") (pintype "bidirectional"))
      (node (ref "R16") (pin "2") (pinfunction "2_2") (pintype "passive"))
    )
    (net (code "72") (name "Net-(MP2225-3V3-FB)") (class "Default")
      (node (ref "C11") (pin "2") (pinfunction "2_2") (pintype "passive"))
      (node (ref "MP2225-3V3") (pin "P$8") (pinfunction "FB_P$8") (pintype "bidirectional"))
      (node (ref "R25") (pin "1") (pinfunction "1_1") (pintype "passive"))
      (node (ref "R26") (pin "1") (pinfunction "1_1") (pintype "passive"))
    )
    (net (code "73") (name "Net-(MP2225-3V3-VCC)") (class "Default")
      (node (ref "C8") (pin "2") (pinfunction "2_2") (pintype "passive"))
      (node (ref "MP2225-3V3") (pin "P$7") (pinfunction "VCC_P$7") (pintype "bidirectional"))
    )
    (net (code "74") (name "Net-(MP2225-5V-BST)") (class "Default")
      (node (ref "C15") (pin "2") (pinfunction "2_2") (pintype "passive"))
      (node (ref "MP2225-5V") (pin "P$5") (pinfunction "BST_P$5") (pintype "bidirectional"))
    )
    (net (code "75") (name "Net-(MP2225-5V-EN)") (class "Default")
      (node (ref "MP2225-5V") (pin "P$6") (pinfunction "EN_P$6") (pintype "bidirectional"))
      (node (ref "R27") (pin "2") (pinfunction "2_2") (pintype "passive"))
    )
    (net (code "76") (name "Net-(MP2225-5V-FB)") (class "Default")
      (node (ref "C16") (pin "2") (pinfunction "2_2") (pintype "passive"))
      (node (ref "MP2225-5V") (pin "P$8") (pinfunction "FB_P$8") (pintype "bidirectional"))
      (node (ref "R28") (pin "1") (pinfunction "1_1") (pintype "passive"))
      (node (ref "R29") (pin "1") (pinfunction "1_1") (pintype "passive"))
    )
    (net (code "77") (name "Net-(MP2225-5V-VCC)") (class "Default")
      (node (ref "C17") (pin "2") (pinfunction "2_2") (pintype "passive"))
      (node (ref "MP2225-5V") (pin "P$7") (pinfunction "VCC_P$7") (pintype "bidirectional"))
    )
    (net (code "78") (name "Net-(U$3-G)") (class "Default")
      (node (ref "R20") (pin "2") (pinfunction "2_2") (pintype "passive"))
      (node (ref "R31") (pin "2") (pinfunction "2_2") (pintype "passive"))
      (node (ref "U$3") (pin "1") (pinfunction "G_1") (pintype "bidirectional"))
    )
    (net (code "79") (name "Net-(U$4-G)") (class "Default")
      (node (ref "R14") (pin "2") (pinfunction "2_2") (pintype "passive"))
      (node (ref "R17") (pin "2") (pinfunction "2_2") (pintype "passive"))
      (node (ref "U$4") (pin "1") (pinfunction "G_1") (pintype "bidirectional"))
    )
    (net (code "80") (name "Net-(U$13-IO5)") (class "Default")
      (node (ref "R2") (pin "1") (pinfunction "1_1") (pintype "passive"))
      (node (ref "U$13") (pin "29") (pinfunction "IO5_29") (pintype "bidirectional"))
    )
    (net (code "81") (name "Net-(U$23-D)") (class "Default")
      (node (ref "R3") (pin "2") (pinfunction "2_2") (pintype "passive"))
      (node (ref "U$23") (pin "3") (pinfunction "D_3") (pintype "bidirectional"))
      (node (ref "U$24") (pin "2") (pinfunction "GND_2") (pintype "bidirectional"))
    )
    (net (code "82") (name "Net-(U$23-G)") (class "Default")
      (node (ref "R32") (pin "1") (pinfunction "1_1") (pintype "passive"))
      (node (ref "R4") (pin "1") (pinfunction "1_1") (pintype "passive"))
      (node (ref "U$23") (pin "1") (pinfunction "G_1") (pintype "bidirectional"))
    )
    (net (code "83") (name "unconnected-(74HC595#2-Q7S-Pad9)") (class "Default")
      (node (ref "74HC595#2") (pin "9") (pinfunction "Q7S_9") (pintype "bidirectional"))
    )
    (net (code "84") (name "unconnected-(74HC595#4-Q3-Pad3)") (class "Default")
      (node (ref "74HC595#4") (pin "3") (pinfunction "Q3_3") (pintype "bidirectional"))
    )
    (net (code "85") (name "unconnected-(74HC595#4-Q4-Pad4)") (class "Default")
      (node (ref "74HC595#4") (pin "4") (pinfunction "Q4_4") (pintype "bidirectional"))
    )
    (net (code "86") (name "unconnected-(74HC595#4-Q5-Pad5)") (class "Default")
      (node (ref "74HC595#4") (pin "5") (pinfunction "Q5_5") (pintype "bidirectional"))
    )
    (net (code "87") (name "unconnected-(74HC595#4-Q6-Pad6)") (class "Default")
      (node (ref "74HC595#4") (pin "6") (pinfunction "Q6_6") (pintype "bidirectional"))
    )
    (net (code "88") (name "unconnected-(74HC595#4-Q7-Pad7)") (class "Default")
      (node (ref "74HC595#4") (pin "7") (pinfunction "Q7_7") (pintype "bidirectional"))
    )
    (net (code "89") (name "unconnected-(U$1-DIO2-Pad8)") (class "Default")
      (node (ref "U$1") (pin "8") (pinfunction "DIO2_8") (pintype "bidirectional"))
    )
    (net (code "90") (name "unconnected-(U$13-CLK-Pad20)") (class "Default")
      (node (ref "U$13") (pin "20") (pinfunction "CLK_20") (pintype "bidirectional"))
    )
    (net (code "91") (name "unconnected-(U$13-CMD-Pad19)") (class "Default")
      (node (ref "U$13") (pin "19") (pinfunction "CMD_19") (pintype "bidirectional"))
    )
    (net (code "92") (name "unconnected-(U$13-IO34-Pad6)") (class "Default")
      (node (ref "U$13") (pin "6") (pinfunction "IO34_6") (pintype "bidirectional"))
    )
    (net (code "93") (name "unconnected-(U$13-SD0-Pad21)") (class "Default")
      (node (ref "U$13") (pin "21") (pinfunction "SD0_21") (pintype "bidirectional"))
    )
    (net (code "94") (name "unconnected-(U$13-SD1-Pad22)") (class "Default")
      (node (ref "U$13") (pin "22") (pinfunction "SD1_22") (pintype "bidirectional"))
    )
    (net (code "95") (name "unconnected-(U$13-SD2-Pad17)") (class "Default")
      (node (ref "U$13") (pin "17") (pinfunction "SD2_17") (pintype "bidirectional"))
    )
    (net (code "96") (name "unconnected-(U$13-SD3-Pad18)") (class "Default")
      (node (ref "U$13") (pin "18") (pinfunction "SD3_18") (pintype "bidirectional"))
    )
    (net (code "97") (name "unconnected-(U$21-12-PadP$12)") (class "Default")
      (node (ref "U$21") (pin "P$12") (pinfunction "12_P$12") (pintype "passive"))
    )
    (net (code "98") (name "unconnected-(U$21-13-PadP$13)") (class "Default")
      (node (ref "U$21") (pin "P$13") (pinfunction "13_P$13") (pintype "passive"))
    )
    (net (code "99") (name "unconnected-(U$21-14-PadP$14)") (class "Default")
      (node (ref "U$21") (pin "P$14") (pinfunction "14_P$14") (pintype "passive"))
    )
    (net (code "100") (name "unconnected-(U$21-15-PadP$15)") (class "Default")
      (node (ref "U$21") (pin "P$15") (pinfunction "15_P$15") (pintype "passive"))
    )
  )
)
